# traffic_lights.net
KiCad netlist of a schematic drawn in EAGLE
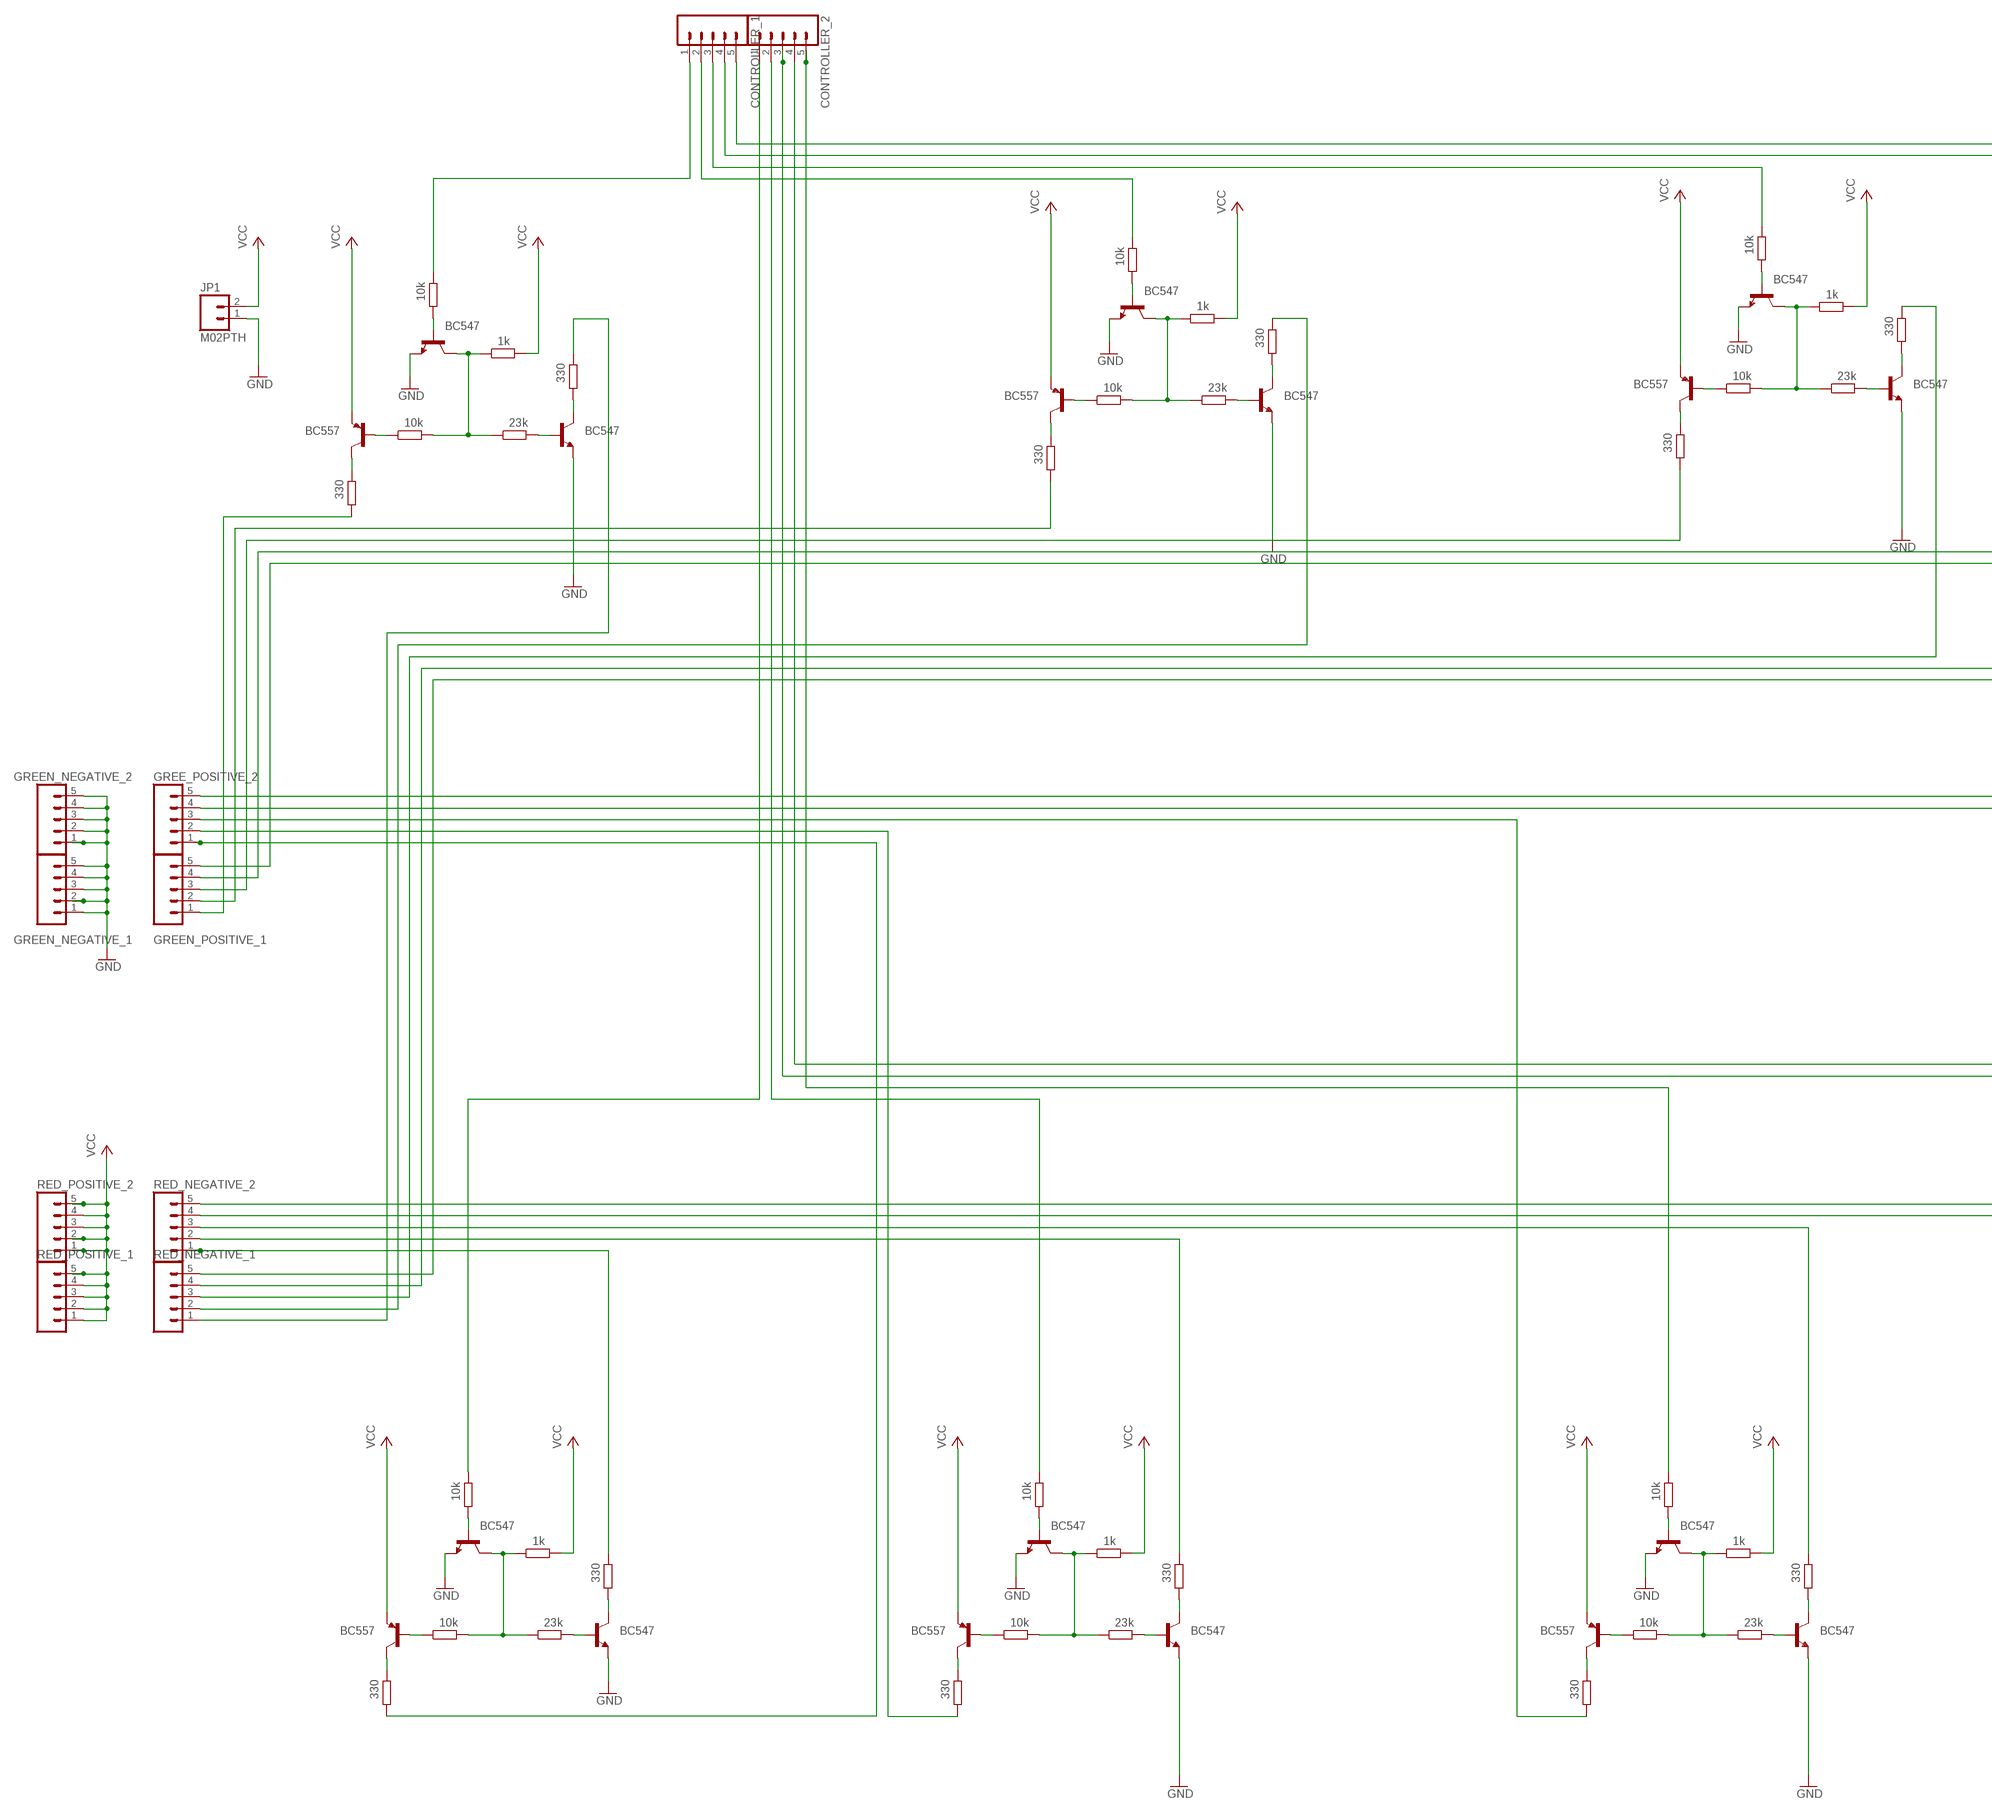
[diagram p0: schematic, sheet 1, part 1 of 2]
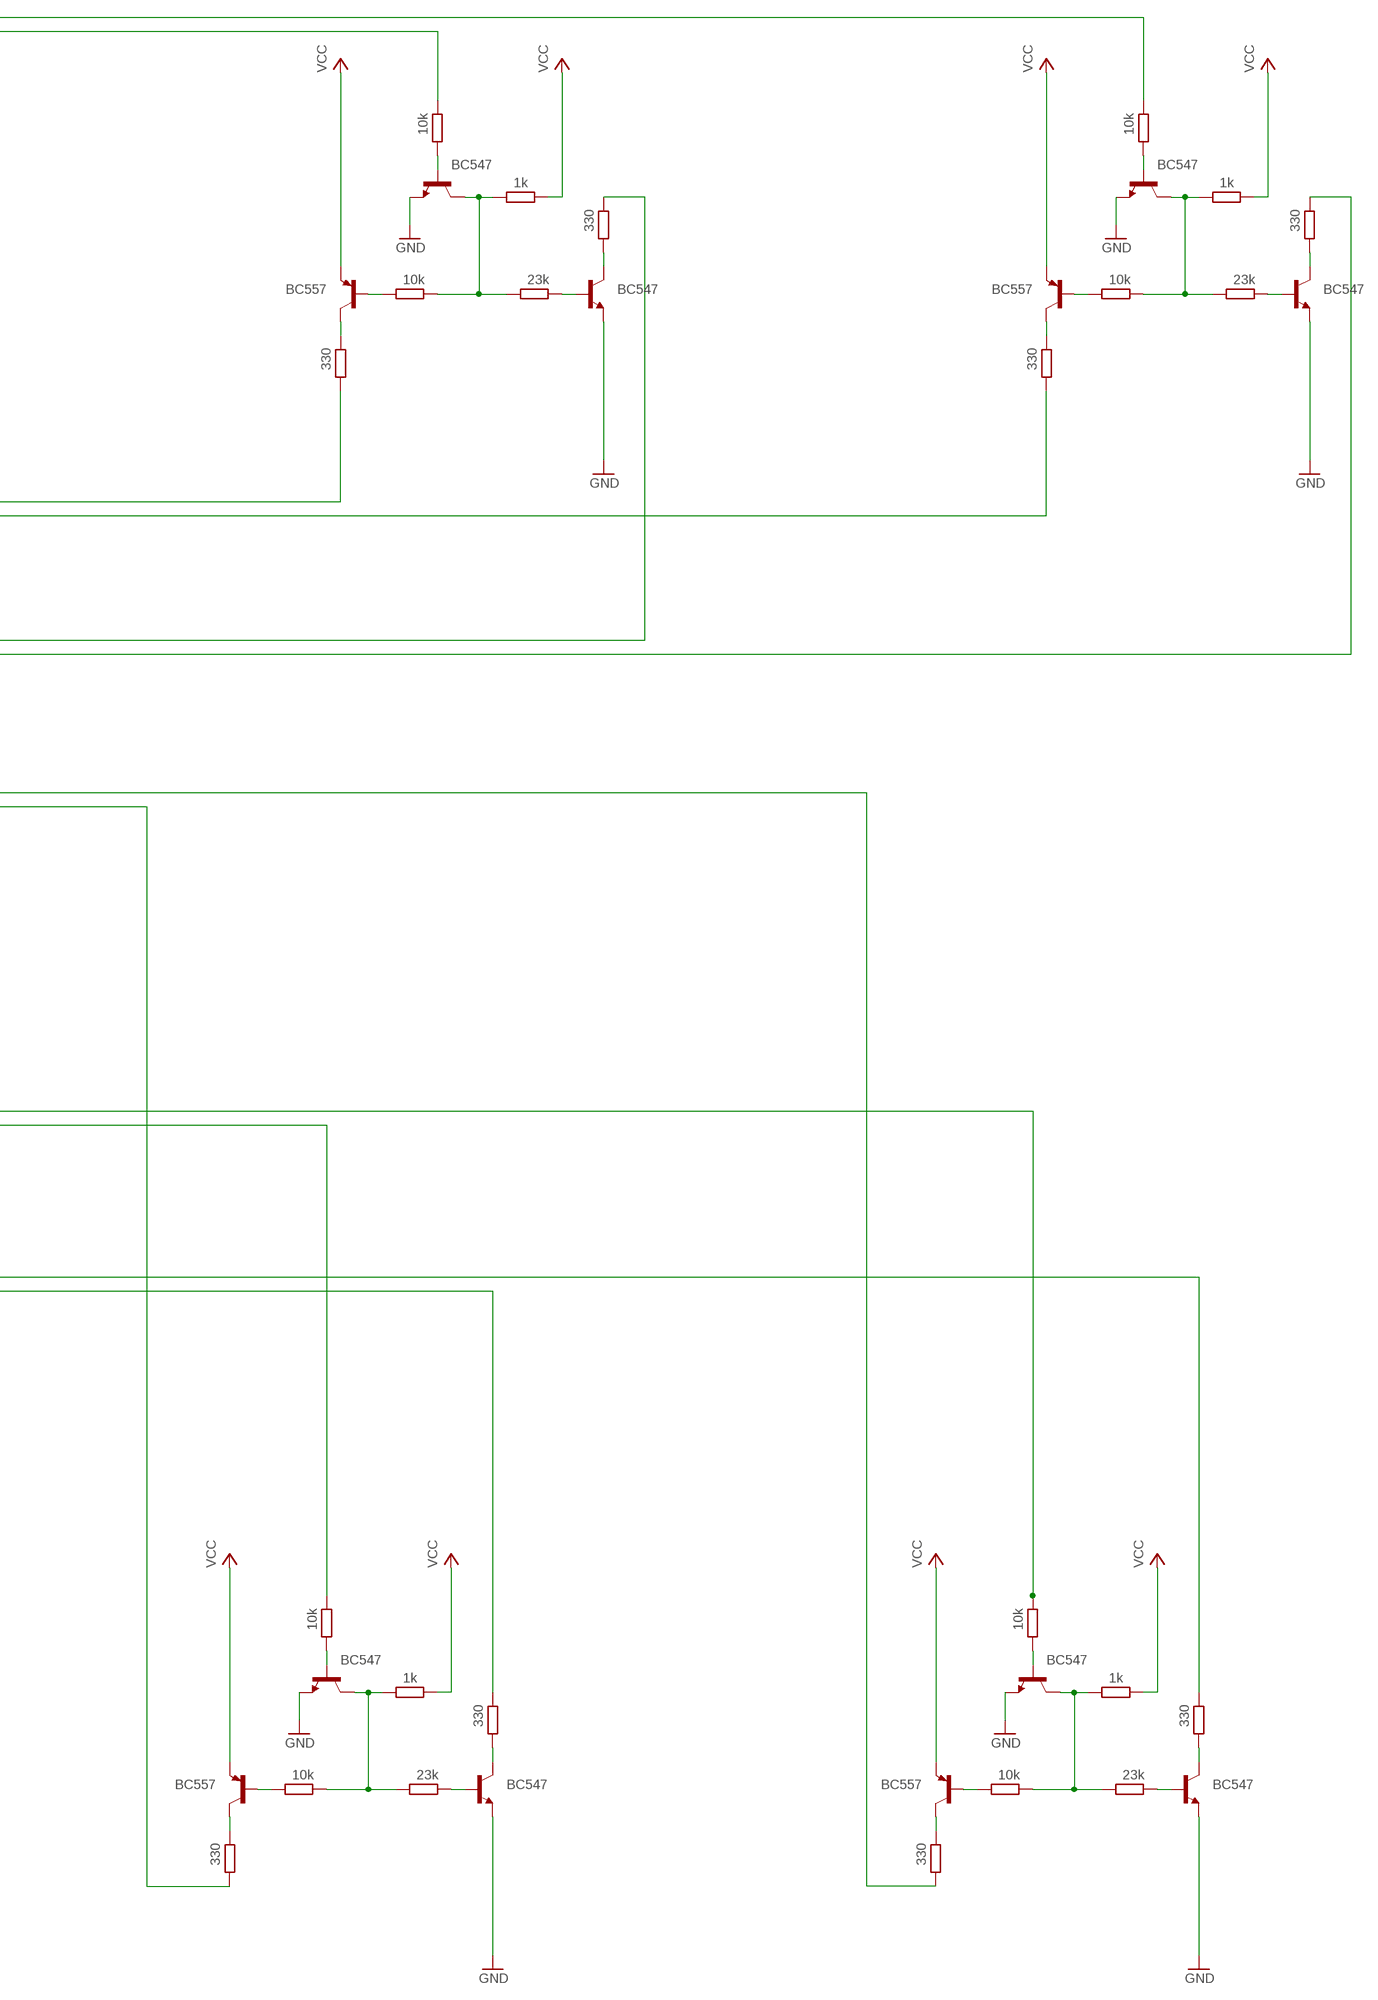
[diagram p1: schematic, sheet 1, part 2 of 2]

(export (version "E")
  (design (tool "Eeschema 10.0.6"))
  (components
    (comp (ref "CONTROLLER_1")
      (value "M05PTH")
      (footprint "eagle-import:1X05")
      (libsource (lib "eagle-import") (part "M05PTH"))
    )
    (comp (ref "CONTROLLER_2")
      (value "M05PTH")
      (footprint "eagle-import:1X05")
      (libsource (lib "eagle-import") (part "M05PTH"))
    )
    (comp (ref "GREEN_NEGATIVE_1")
      (value "M05PTH")
      (footprint "eagle-import:1X05")
      (libsource (lib "eagle-import") (part "M05PTH"))
    )
    (comp (ref "GREEN_NEGATIVE_2")
      (value "M05PTH")
      (footprint "eagle-import:1X05")
      (libsource (lib "eagle-import") (part "M05PTH"))
    )
    (comp (ref "GREEN_POSITIVE_1")
      (value "M05PTH")
      (footprint "eagle-import:1X05")
      (libsource (lib "eagle-import") (part "M05PTH"))
    )
    (comp (ref "GREE_POSITIVE_2")
      (value "M05PTH")
      (footprint "eagle-import:1X05")
      (libsource (lib "eagle-import") (part "M05PTH"))
    )
    (comp (ref "JP1")
      (value "M02PTH")
      (footprint "eagle-import:1X02")
      (libsource (lib "eagle-import") (part "M02PTH"))
    )
    (comp (ref "RC1")
      (value "10k")
      (footprint "eagle-import:0207_10")
      (libsource (lib "eagle-import") (part "R-EU_0207/10"))
    )
    (comp (ref "RC2")
      (value "1k")
      (footprint "eagle-import:0207_10")
      (libsource (lib "eagle-import") (part "R-EU_0207/10"))
    )
    (comp (ref "RC3")
      (value "23k")
      (footprint "eagle-import:0207_10")
      (libsource (lib "eagle-import") (part "R-EU_0207/10"))
    )
    (comp (ref "RC4")
      (value "10k")
      (footprint "eagle-import:0207_10")
      (libsource (lib "eagle-import") (part "R-EU_0207/10"))
    )
    (comp (ref "RC5")
      (value "330")
      (footprint "eagle-import:0207_10")
      (libsource (lib "eagle-import") (part "R-EU_0207/10"))
    )
    (comp (ref "RC6")
      (value "330")
      (footprint "eagle-import:0207_10")
      (libsource (lib "eagle-import") (part "R-EU_0207/10"))
    )
    (comp (ref "RC21")
      (value "10k")
      (footprint "eagle-import:0207_10")
      (libsource (lib "eagle-import") (part "R-EU_0207/10"))
    )
    (comp (ref "RC22")
      (value "1k")
      (footprint "eagle-import:0207_10")
      (libsource (lib "eagle-import") (part "R-EU_0207/10"))
    )
    (comp (ref "RC23")
      (value "23k")
      (footprint "eagle-import:0207_10")
      (libsource (lib "eagle-import") (part "R-EU_0207/10"))
    )
    (comp (ref "RC24")
      (value "10k")
      (footprint "eagle-import:0207_10")
      (libsource (lib "eagle-import") (part "R-EU_0207/10"))
    )
    (comp (ref "RC25")
      (value "330")
      (footprint "eagle-import:0207_10")
      (libsource (lib "eagle-import") (part "R-EU_0207/10"))
    )
    (comp (ref "RC26")
      (value "330")
      (footprint "eagle-import:0207_10")
      (libsource (lib "eagle-import") (part "R-EU_0207/10"))
    )
    (comp (ref "RC31")
      (value "10k")
      (footprint "eagle-import:0207_10")
      (libsource (lib "eagle-import") (part "R-EU_0207/10"))
    )
    (comp (ref "RC32")
      (value "1k")
      (footprint "eagle-import:0207_10")
      (libsource (lib "eagle-import") (part "R-EU_0207/10"))
    )
    (comp (ref "RC33")
      (value "23k")
      (footprint "eagle-import:0207_10")
      (libsource (lib "eagle-import") (part "R-EU_0207/10"))
    )
    (comp (ref "RC34")
      (value "10k")
      (footprint "eagle-import:0207_10")
      (libsource (lib "eagle-import") (part "R-EU_0207/10"))
    )
    (comp (ref "RC35")
      (value "330")
      (footprint "eagle-import:0207_10")
      (libsource (lib "eagle-import") (part "R-EU_0207/10"))
    )
    (comp (ref "RC36")
      (value "330")
      (footprint "eagle-import:0207_10")
      (libsource (lib "eagle-import") (part "R-EU_0207/10"))
    )
    (comp (ref "RC41")
      (value "10k")
      (footprint "eagle-import:0207_10")
      (libsource (lib "eagle-import") (part "R-EU_0207/10"))
    )
    (comp (ref "RC42")
      (value "1k")
      (footprint "eagle-import:0207_10")
      (libsource (lib "eagle-import") (part "R-EU_0207/10"))
    )
    (comp (ref "RC43")
      (value "23k")
      (footprint "eagle-import:0207_10")
      (libsource (lib "eagle-import") (part "R-EU_0207/10"))
    )
    (comp (ref "RC44")
      (value "10k")
      (footprint "eagle-import:0207_10")
      (libsource (lib "eagle-import") (part "R-EU_0207/10"))
    )
    (comp (ref "RC45")
      (value "330")
      (footprint "eagle-import:0207_10")
      (libsource (lib "eagle-import") (part "R-EU_0207/10"))
    )
    (comp (ref "RC46")
      (value "330")
      (footprint "eagle-import:0207_10")
      (libsource (lib "eagle-import") (part "R-EU_0207/10"))
    )
    (comp (ref "RC51")
      (value "10k")
      (footprint "eagle-import:0207_10")
      (libsource (lib "eagle-import") (part "R-EU_0207/10"))
    )
    (comp (ref "RC52")
      (value "1k")
      (footprint "eagle-import:0207_10")
      (libsource (lib "eagle-import") (part "R-EU_0207/10"))
    )
    (comp (ref "RC53")
      (value "23k")
      (footprint "eagle-import:0207_10")
      (libsource (lib "eagle-import") (part "R-EU_0207/10"))
    )
    (comp (ref "RC54")
      (value "10k")
      (footprint "eagle-import:0207_10")
      (libsource (lib "eagle-import") (part "R-EU_0207/10"))
    )
    (comp (ref "RC55")
      (value "330")
      (footprint "eagle-import:0207_10")
      (libsource (lib "eagle-import") (part "R-EU_0207/10"))
    )
    (comp (ref "RC56")
      (value "330")
      (footprint "eagle-import:0207_10")
      (libsource (lib "eagle-import") (part "R-EU_0207/10"))
    )
    (comp (ref "RC61")
      (value "10k")
      (footprint "eagle-import:0207_10")
      (libsource (lib "eagle-import") (part "R-EU_0207/10"))
    )
    (comp (ref "RC62")
      (value "1k")
      (footprint "eagle-import:0207_10")
      (libsource (lib "eagle-import") (part "R-EU_0207/10"))
    )
    (comp (ref "RC63")
      (value "23k")
      (footprint "eagle-import:0207_10")
      (libsource (lib "eagle-import") (part "R-EU_0207/10"))
    )
    (comp (ref "RC64")
      (value "10k")
      (footprint "eagle-import:0207_10")
      (libsource (lib "eagle-import") (part "R-EU_0207/10"))
    )
    (comp (ref "RC65")
      (value "330")
      (footprint "eagle-import:0207_10")
      (libsource (lib "eagle-import") (part "R-EU_0207/10"))
    )
    (comp (ref "RC66")
      (value "330")
      (footprint "eagle-import:0207_10")
      (libsource (lib "eagle-import") (part "R-EU_0207/10"))
    )
    (comp (ref "RC71")
      (value "10k")
      (footprint "eagle-import:0207_10")
      (libsource (lib "eagle-import") (part "R-EU_0207/10"))
    )
    (comp (ref "RC72")
      (value "1k")
      (footprint "eagle-import:0207_10")
      (libsource (lib "eagle-import") (part "R-EU_0207/10"))
    )
    (comp (ref "RC73")
      (value "23k")
      (footprint "eagle-import:0207_10")
      (libsource (lib "eagle-import") (part "R-EU_0207/10"))
    )
    (comp (ref "RC74")
      (value "10k")
      (footprint "eagle-import:0207_10")
      (libsource (lib "eagle-import") (part "R-EU_0207/10"))
    )
    (comp (ref "RC75")
      (value "330")
      (footprint "eagle-import:0207_10")
      (libsource (lib "eagle-import") (part "R-EU_0207/10"))
    )
    (comp (ref "RC76")
      (value "330")
      (footprint "eagle-import:0207_10")
      (libsource (lib "eagle-import") (part "R-EU_0207/10"))
    )
    (comp (ref "RC81")
      (value "10k")
      (footprint "eagle-import:0207_10")
      (libsource (lib "eagle-import") (part "R-EU_0207/10"))
    )
    (comp (ref "RC82")
      (value "1k")
      (footprint "eagle-import:0207_10")
      (libsource (lib "eagle-import") (part "R-EU_0207/10"))
    )
    (comp (ref "RC83")
      (value "23k")
      (footprint "eagle-import:0207_10")
      (libsource (lib "eagle-import") (part "R-EU_0207/10"))
    )
    (comp (ref "RC84")
      (value "10k")
      (footprint "eagle-import:0207_10")
      (libsource (lib "eagle-import") (part "R-EU_0207/10"))
    )
    (comp (ref "RC85")
      (value "330")
      (footprint "eagle-import:0207_10")
      (libsource (lib "eagle-import") (part "R-EU_0207/10"))
    )
    (comp (ref "RC86")
      (value "330")
      (footprint "eagle-import:0207_10")
      (libsource (lib "eagle-import") (part "R-EU_0207/10"))
    )
    (comp (ref "RC91")
      (value "10k")
      (footprint "eagle-import:0207_10")
      (libsource (lib "eagle-import") (part "R-EU_0207/10"))
    )
    (comp (ref "RC92")
      (value "1k")
      (footprint "eagle-import:0207_10")
      (libsource (lib "eagle-import") (part "R-EU_0207/10"))
    )
    (comp (ref "RC93")
      (value "23k")
      (footprint "eagle-import:0207_10")
      (libsource (lib "eagle-import") (part "R-EU_0207/10"))
    )
    (comp (ref "RC94")
      (value "10k")
      (footprint "eagle-import:0207_10")
      (libsource (lib "eagle-import") (part "R-EU_0207/10"))
    )
    (comp (ref "RC95")
      (value "330")
      (footprint "eagle-import:0207_10")
      (libsource (lib "eagle-import") (part "R-EU_0207/10"))
    )
    (comp (ref "RC96")
      (value "330")
      (footprint "eagle-import:0207_10")
      (libsource (lib "eagle-import") (part "R-EU_0207/10"))
    )
    (comp (ref "RC101")
      (value "10k")
      (footprint "eagle-import:0207_10")
      (libsource (lib "eagle-import") (part "R-EU_0207/10"))
    )
    (comp (ref "RC102")
      (value "1k")
      (footprint "eagle-import:0207_10")
      (libsource (lib "eagle-import") (part "R-EU_0207/10"))
    )
    (comp (ref "RC103")
      (value "23k")
      (footprint "eagle-import:0207_10")
      (libsource (lib "eagle-import") (part "R-EU_0207/10"))
    )
    (comp (ref "RC104")
      (value "10k")
      (footprint "eagle-import:0207_10")
      (libsource (lib "eagle-import") (part "R-EU_0207/10"))
    )
    (comp (ref "RC105")
      (value "330")
      (footprint "eagle-import:0207_10")
      (libsource (lib "eagle-import") (part "R-EU_0207/10"))
    )
    (comp (ref "RC106")
      (value "330")
      (footprint "eagle-import:0207_10")
      (libsource (lib "eagle-import") (part "R-EU_0207/10"))
    )
    (comp (ref "RED_NEGATIVE_1")
      (value "M05PTH")
      (footprint "eagle-import:1X05")
      (libsource (lib "eagle-import") (part "M05PTH"))
    )
    (comp (ref "RED_NEGATIVE_2")
      (value "M05PTH")
      (footprint "eagle-import:1X05")
      (libsource (lib "eagle-import") (part "M05PTH"))
    )
    (comp (ref "RED_POSITIVE_1")
      (value "M05PTH")
      (footprint "eagle-import:1X05")
      (libsource (lib "eagle-import") (part "M05PTH"))
    )
    (comp (ref "RED_POSITIVE_2")
      (value "M05PTH")
      (footprint "eagle-import:1X05")
      (libsource (lib "eagle-import") (part "M05PTH"))
    )
    (comp (ref "TCTRL1")
      (value "BC547")
      (footprint "eagle-import:TO92")
      (libsource (lib "eagle-import") (part "BC547"))
    )
    (comp (ref "TCTRL2")
      (value "BC547")
      (footprint "eagle-import:TO92")
      (libsource (lib "eagle-import") (part "BC547"))
    )
    (comp (ref "TCTRL3")
      (value "BC547")
      (footprint "eagle-import:TO92")
      (libsource (lib "eagle-import") (part "BC547"))
    )
    (comp (ref "TCTRL4")
      (value "BC547")
      (footprint "eagle-import:TO92")
      (libsource (lib "eagle-import") (part "BC547"))
    )
    (comp (ref "TCTRL5")
      (value "BC547")
      (footprint "eagle-import:TO92")
      (libsource (lib "eagle-import") (part "BC547"))
    )
    (comp (ref "TCTRL6")
      (value "BC547")
      (footprint "eagle-import:TO92")
      (libsource (lib "eagle-import") (part "BC547"))
    )
    (comp (ref "TCTRL7")
      (value "BC547")
      (footprint "eagle-import:TO92")
      (libsource (lib "eagle-import") (part "BC547"))
    )
    (comp (ref "TCTRL8")
      (value "BC547")
      (footprint "eagle-import:TO92")
      (libsource (lib "eagle-import") (part "BC547"))
    )
    (comp (ref "TCTRL9")
      (value "BC547")
      (footprint "eagle-import:TO92")
      (libsource (lib "eagle-import") (part "BC547"))
    )
    (comp (ref "TCTRL10")
      (value "BC547")
      (footprint "eagle-import:TO92")
      (libsource (lib "eagle-import") (part "BC547"))
    )
    (comp (ref "TGR1")
      (value "BC547")
      (footprint "eagle-import:TO92")
      (libsource (lib "eagle-import") (part "BC547"))
    )
    (comp (ref "TGR2")
      (value "BC547")
      (footprint "eagle-import:TO92")
      (libsource (lib "eagle-import") (part "BC547"))
    )
    (comp (ref "TGR3")
      (value "BC547")
      (footprint "eagle-import:TO92")
      (libsource (lib "eagle-import") (part "BC547"))
    )
    (comp (ref "TGR4")
      (value "BC547")
      (footprint "eagle-import:TO92")
      (libsource (lib "eagle-import") (part "BC547"))
    )
    (comp (ref "TGR5")
      (value "BC547")
      (footprint "eagle-import:TO92")
      (libsource (lib "eagle-import") (part "BC547"))
    )
    (comp (ref "TGR6")
      (value "BC547")
      (footprint "eagle-import:TO92")
      (libsource (lib "eagle-import") (part "BC547"))
    )
    (comp (ref "TGR7")
      (value "BC547")
      (footprint "eagle-import:TO92")
      (libsource (lib "eagle-import") (part "BC547"))
    )
    (comp (ref "TGR8")
      (value "BC547")
      (footprint "eagle-import:TO92")
      (libsource (lib "eagle-import") (part "BC547"))
    )
    (comp (ref "TGR9")
      (value "BC547")
      (footprint "eagle-import:TO92")
      (libsource (lib "eagle-import") (part "BC547"))
    )
    (comp (ref "TGR10")
      (value "BC547")
      (footprint "eagle-import:TO92")
      (libsource (lib "eagle-import") (part "BC547"))
    )
    (comp (ref "TR1")
      (value "BC557")
      (footprint "eagle-import:TO92")
      (libsource (lib "eagle-import") (part "BC557"))
    )
    (comp (ref "TR2")
      (value "BC557")
      (footprint "eagle-import:TO92")
      (libsource (lib "eagle-import") (part "BC557"))
    )
    (comp (ref "TR3")
      (value "BC557")
      (footprint "eagle-import:TO92")
      (libsource (lib "eagle-import") (part "BC557"))
    )
    (comp (ref "TR4")
      (value "BC557")
      (footprint "eagle-import:TO92")
      (libsource (lib "eagle-import") (part "BC557"))
    )
    (comp (ref "TR5")
      (value "BC557")
      (footprint "eagle-import:TO92")
      (libsource (lib "eagle-import") (part "BC557"))
    )
    (comp (ref "TR6")
      (value "BC557")
      (footprint "eagle-import:TO92")
      (libsource (lib "eagle-import") (part "BC557"))
    )
    (comp (ref "TR7")
      (value "BC557")
      (footprint "eagle-import:TO92")
      (libsource (lib "eagle-import") (part "BC557"))
    )
    (comp (ref "TR8")
      (value "BC557")
      (footprint "eagle-import:TO92")
      (libsource (lib "eagle-import") (part "BC557"))
    )
    (comp (ref "TR9")
      (value "BC557")
      (footprint "eagle-import:TO92")
      (libsource (lib "eagle-import") (part "BC557"))
    )
    (comp (ref "TR10")
      (value "BC557")
      (footprint "eagle-import:TO92")
      (libsource (lib "eagle-import") (part "BC557"))
    )
  )
  (nets
    (net (code "1") (name "GND") (class "Default")
      (node (ref "GREEN_NEGATIVE_1") (pin "1") (pinfunction "1_1") (pintype "passive"))
      (node (ref "GREEN_NEGATIVE_1") (pin "2") (pinfunction "2_2") (pintype "passive"))
      (node (ref "GREEN_NEGATIVE_1") (pin "3") (pinfunction "3_3") (pintype "passive"))
      (node (ref "GREEN_NEGATIVE_1") (pin "4") (pinfunction "4_4") (pintype "passive"))
      (node (ref "GREEN_NEGATIVE_1") (pin "5") (pinfunction "5_5") (pintype "passive"))
      (node (ref "GREEN_NEGATIVE_2") (pin "1") (pinfunction "1_1") (pintype "passive"))
      (node (ref "GREEN_NEGATIVE_2") (pin "2") (pinfunction "2_2") (pintype "passive"))
      (node (ref "GREEN_NEGATIVE_2") (pin "3") (pinfunction "3_3") (pintype "passive"))
      (node (ref "GREEN_NEGATIVE_2") (pin "4") (pinfunction "4_4") (pintype "passive"))
      (node (ref "GREEN_NEGATIVE_2") (pin "5") (pinfunction "5_5") (pintype "passive"))
      (node (ref "JP1") (pin "1") (pinfunction "1_1") (pintype "passive"))
      (node (ref "TCTRL1") (pin "1") (pinfunction "E_1") (pintype "passive"))
      (node (ref "TCTRL10") (pin "1") (pinfunction "E_1") (pintype "passive"))
      (node (ref "TCTRL2") (pin "1") (pinfunction "E_1") (pintype "passive"))
      (node (ref "TCTRL3") (pin "1") (pinfunction "E_1") (pintype "passive"))
      (node (ref "TCTRL4") (pin "1") (pinfunction "E_1") (pintype "passive"))
      (node (ref "TCTRL5") (pin "1") (pinfunction "E_1") (pintype "passive"))
      (node (ref "TCTRL6") (pin "1") (pinfunction "E_1") (pintype "passive"))
      (node (ref "TCTRL7") (pin "1") (pinfunction "E_1") (pintype "passive"))
      (node (ref "TCTRL8") (pin "1") (pinfunction "E_1") (pintype "passive"))
      (node (ref "TCTRL9") (pin "1") (pinfunction "E_1") (pintype "passive"))
      (node (ref "TGR1") (pin "1") (pinfunction "E_1") (pintype "passive"))
      (node (ref "TGR10") (pin "1") (pinfunction "E_1") (pintype "passive"))
      (node (ref "TGR2") (pin "1") (pinfunction "E_1") (pintype "passive"))
      (node (ref "TGR3") (pin "1") (pinfunction "E_1") (pintype "passive"))
      (node (ref "TGR4") (pin "1") (pinfunction "E_1") (pintype "passive"))
      (node (ref "TGR5") (pin "1") (pinfunction "E_1") (pintype "passive"))
      (node (ref "TGR6") (pin "1") (pinfunction "E_1") (pintype "passive"))
      (node (ref "TGR7") (pin "1") (pinfunction "E_1") (pintype "passive"))
      (node (ref "TGR8") (pin "1") (pinfunction "E_1") (pintype "passive"))
      (node (ref "TGR9") (pin "1") (pinfunction "E_1") (pintype "passive"))
    )
    (net (code "2") (name "Net-(CONTROLLER_1-Pad1)") (class "Default")
      (node (ref "CONTROLLER_1") (pin "1") (pinfunction "1_1") (pintype "passive"))
      (node (ref "RC1") (pin "2") (pinfunction "2_2") (pintype "passive"))
    )
    (net (code "3") (name "Net-(CONTROLLER_1-Pad2)") (class "Default")
      (node (ref "CONTROLLER_1") (pin "2") (pinfunction "2_2") (pintype "passive"))
      (node (ref "RC21") (pin "2") (pinfunction "2_2") (pintype "passive"))
    )
    (net (code "4") (name "Net-(CONTROLLER_1-Pad3)") (class "Default")
      (node (ref "CONTROLLER_1") (pin "3") (pinfunction "3_3") (pintype "passive"))
      (node (ref "RC31") (pin "2") (pinfunction "2_2") (pintype "passive"))
    )
    (net (code "5") (name "Net-(CONTROLLER_1-Pad4)") (class "Default")
      (node (ref "CONTROLLER_1") (pin "4") (pinfunction "4_4") (pintype "passive"))
      (node (ref "RC41") (pin "2") (pinfunction "2_2") (pintype "passive"))
    )
    (net (code "6") (name "Net-(CONTROLLER_1-Pad5)") (class "Default")
      (node (ref "CONTROLLER_1") (pin "5") (pinfunction "5_5") (pintype "passive"))
      (node (ref "RC51") (pin "2") (pinfunction "2_2") (pintype "passive"))
    )
    (net (code "7") (name "Net-(CONTROLLER_2-Pad1)") (class "Default")
      (node (ref "CONTROLLER_2") (pin "1") (pinfunction "1_1") (pintype "passive"))
      (node (ref "RC61") (pin "2") (pinfunction "2_2") (pintype "passive"))
    )
    (net (code "8") (name "Net-(CONTROLLER_2-Pad2)") (class "Default")
      (node (ref "CONTROLLER_2") (pin "2") (pinfunction "2_2") (pintype "passive"))
      (node (ref "RC71") (pin "2") (pinfunction "2_2") (pintype "passive"))
    )
    (net (code "9") (name "Net-(CONTROLLER_2-Pad3)") (class "Default")
      (node (ref "CONTROLLER_2") (pin "3") (pinfunction "3_3") (pintype "passive"))
      (node (ref "RC91") (pin "2") (pinfunction "2_2") (pintype "passive"))
    )
    (net (code "10") (name "Net-(CONTROLLER_2-Pad4)") (class "Default")
      (node (ref "CONTROLLER_2") (pin "4") (pinfunction "4_4") (pintype "passive"))
      (node (ref "RC101") (pin "2") (pinfunction "2_2") (pintype "passive"))
    )
    (net (code "11") (name "Net-(CONTROLLER_2-Pad5)") (class "Default")
      (node (ref "CONTROLLER_2") (pin "5") (pinfunction "5_5") (pintype "passive"))
      (node (ref "RC81") (pin "2") (pinfunction "2_2") (pintype "passive"))
    )
    (net (code "12") (name "Net-(GREEN_POSITIVE_1-Pad1)") (class "Default")
      (node (ref "GREEN_POSITIVE_1") (pin "1") (pinfunction "1_1") (pintype "passive"))
      (node (ref "RC6") (pin "1") (pinfunction "1_1") (pintype "passive"))
    )
    (net (code "13") (name "Net-(GREEN_POSITIVE_1-Pad2)") (class "Default")
      (node (ref "GREEN_POSITIVE_1") (pin "2") (pinfunction "2_2") (pintype "passive"))
      (node (ref "RC26") (pin "1") (pinfunction "1_1") (pintype "passive"))
    )
    (net (code "14") (name "Net-(GREEN_POSITIVE_1-Pad3)") (class "Default")
      (node (ref "GREEN_POSITIVE_1") (pin "3") (pinfunction "3_3") (pintype "passive"))
      (node (ref "RC36") (pin "1") (pinfunction "1_1") (pintype "passive"))
    )
    (net (code "15") (name "Net-(GREEN_POSITIVE_1-Pad4)") (class "Default")
      (node (ref "GREEN_POSITIVE_1") (pin "4") (pinfunction "4_4") (pintype "passive"))
      (node (ref "RC46") (pin "1") (pinfunction "1_1") (pintype "passive"))
    )
    (net (code "16") (name "Net-(GREEN_POSITIVE_1-Pad5)") (class "Default")
      (node (ref "GREEN_POSITIVE_1") (pin "5") (pinfunction "5_5") (pintype "passive"))
      (node (ref "RC56") (pin "1") (pinfunction "1_1") (pintype "passive"))
    )
    (net (code "17") (name "Net-(GREE_POSITIVE_2-Pad1)") (class "Default")
      (node (ref "GREE_POSITIVE_2") (pin "1") (pinfunction "1_1") (pintype "passive"))
      (node (ref "RC66") (pin "1") (pinfunction "1_1") (pintype "passive"))
    )
    (net (code "18") (name "Net-(GREE_POSITIVE_2-Pad2)") (class "Default")
      (node (ref "GREE_POSITIVE_2") (pin "2") (pinfunction "2_2") (pintype "passive"))
      (node (ref "RC76") (pin "1") (pinfunction "1_1") (pintype "passive"))
    )
    (net (code "19") (name "Net-(GREE_POSITIVE_2-Pad3)") (class "Default")
      (node (ref "GREE_POSITIVE_2") (pin "3") (pinfunction "3_3") (pintype "passive"))
      (node (ref "RC86") (pin "1") (pinfunction "1_1") (pintype "passive"))
    )
    (net (code "20") (name "Net-(GREE_POSITIVE_2-Pad4)") (class "Default")
      (node (ref "GREE_POSITIVE_2") (pin "4") (pinfunction "4_4") (pintype "passive"))
      (node (ref "RC96") (pin "1") (pinfunction "1_1") (pintype "passive"))
    )
    (net (code "21") (name "Net-(GREE_POSITIVE_2-Pad5)") (class "Default")
      (node (ref "GREE_POSITIVE_2") (pin "5") (pinfunction "5_5") (pintype "passive"))
      (node (ref "RC106") (pin "1") (pinfunction "1_1") (pintype "passive"))
    )
    (net (code "22") (name "Net-(RC5-Pad2)") (class "Default")
      (node (ref "RC5") (pin "2") (pinfunction "2_2") (pintype "passive"))
      (node (ref "RED_NEGATIVE_1") (pin "1") (pinfunction "1_1") (pintype "passive"))
    )
    (net (code "23") (name "Net-(RC25-Pad2)") (class "Default")
      (node (ref "RC25") (pin "2") (pinfunction "2_2") (pintype "passive"))
      (node (ref "RED_NEGATIVE_1") (pin "2") (pinfunction "2_2") (pintype "passive"))
    )
    (net (code "24") (name "Net-(RC35-Pad2)") (class "Default")
      (node (ref "RC35") (pin "2") (pinfunction "2_2") (pintype "passive"))
      (node (ref "RED_NEGATIVE_1") (pin "3") (pinfunction "3_3") (pintype "passive"))
    )
    (net (code "25") (name "Net-(RC45-Pad2)") (class "Default")
      (node (ref "RC45") (pin "2") (pinfunction "2_2") (pintype "passive"))
      (node (ref "RED_NEGATIVE_1") (pin "4") (pinfunction "4_4") (pintype "passive"))
    )
    (net (code "26") (name "Net-(RC55-Pad2)") (class "Default")
      (node (ref "RC55") (pin "2") (pinfunction "2_2") (pintype "passive"))
      (node (ref "RED_NEGATIVE_1") (pin "5") (pinfunction "5_5") (pintype "passive"))
    )
    (net (code "27") (name "Net-(RC65-Pad2)") (class "Default")
      (node (ref "RC65") (pin "2") (pinfunction "2_2") (pintype "passive"))
      (node (ref "RED_NEGATIVE_2") (pin "1") (pinfunction "1_1") (pintype "passive"))
    )
    (net (code "28") (name "Net-(RC75-Pad2)") (class "Default")
      (node (ref "RC75") (pin "2") (pinfunction "2_2") (pintype "passive"))
      (node (ref "RED_NEGATIVE_2") (pin "2") (pinfunction "2_2") (pintype "passive"))
    )
    (net (code "29") (name "Net-(RC85-Pad2)") (class "Default")
      (node (ref "RC85") (pin "2") (pinfunction "2_2") (pintype "passive"))
      (node (ref "RED_NEGATIVE_2") (pin "3") (pinfunction "3_3") (pintype "passive"))
    )
    (net (code "30") (name "Net-(RC95-Pad2)") (class "Default")
      (node (ref "RC95") (pin "2") (pinfunction "2_2") (pintype "passive"))
      (node (ref "RED_NEGATIVE_2") (pin "4") (pinfunction "4_4") (pintype "passive"))
    )
    (net (code "31") (name "Net-(RC105-Pad2)") (class "Default")
      (node (ref "RC105") (pin "2") (pinfunction "2_2") (pintype "passive"))
      (node (ref "RED_NEGATIVE_2") (pin "5") (pinfunction "5_5") (pintype "passive"))
    )
    (net (code "32") (name "Net-(TCTRL1-B)") (class "Default")
      (node (ref "RC1") (pin "1") (pinfunction "1_1") (pintype "passive"))
      (node (ref "TCTRL1") (pin "2") (pinfunction "B_2") (pintype "passive"))
    )
    (net (code "33") (name "Net-(TCTRL1-C)") (class "Default")
      (node (ref "RC2") (pin "1") (pinfunction "1_1") (pintype "passive"))
      (node (ref "RC3") (pin "1") (pinfunction "1_1") (pintype "passive"))
      (node (ref "RC4") (pin "2") (pinfunction "2_2") (pintype "passive"))
      (node (ref "TCTRL1") (pin "3") (pinfunction "C_3") (pintype "passive"))
    )
    (net (code "34") (name "Net-(TCTRL2-B)") (class "Default")
      (node (ref "RC21") (pin "1") (pinfunction "1_1") (pintype "passive"))
      (node (ref "TCTRL2") (pin "2") (pinfunction "B_2") (pintype "passive"))
    )
    (net (code "35") (name "Net-(TCTRL2-C)") (class "Default")
      (node (ref "RC22") (pin "1") (pinfunction "1_1") (pintype "passive"))
      (node (ref "RC23") (pin "1") (pinfunction "1_1") (pintype "passive"))
      (node (ref "RC24") (pin "2") (pinfunction "2_2") (pintype "passive"))
      (node (ref "TCTRL2") (pin "3") (pinfunction "C_3") (pintype "passive"))
    )
    (net (code "36") (name "Net-(TCTRL3-B)") (class "Default")
      (node (ref "RC31") (pin "1") (pinfunction "1_1") (pintype "passive"))
      (node (ref "TCTRL3") (pin "2") (pinfunction "B_2") (pintype "passive"))
    )
    (net (code "37") (name "Net-(TCTRL3-C)") (class "Default")
      (node (ref "RC32") (pin "1") (pinfunction "1_1") (pintype "passive"))
      (node (ref "RC33") (pin "1") (pinfunction "1_1") (pintype "passive"))
      (node (ref "RC34") (pin "2") (pinfunction "2_2") (pintype "passive"))
      (node (ref "TCTRL3") (pin "3") (pinfunction "C_3") (pintype "passive"))
    )
    (net (code "38") (name "Net-(TCTRL4-B)") (class "Default")
      (node (ref "RC41") (pin "1") (pinfunction "1_1") (pintype "passive"))
      (node (ref "TCTRL4") (pin "2") (pinfunction "B_2") (pintype "passive"))
    )
    (net (code "39") (name "Net-(TCTRL4-C)") (class "Default")
      (node (ref "RC42") (pin "1") (pinfunction "1_1") (pintype "passive"))
      (node (ref "RC43") (pin "1") (pinfunction "1_1") (pintype "passive"))
      (node (ref "RC44") (pin "2") (pinfunction "2_2") (pintype "passive"))
      (node (ref "TCTRL4") (pin "3") (pinfunction "C_3") (pintype "passive"))
    )
    (net (code "40") (name "Net-(TCTRL5-B)") (class "Default")
      (node (ref "RC51") (pin "1") (pinfunction "1_1") (pintype "passive"))
      (node (ref "TCTRL5") (pin "2") (pinfunction "B_2") (pintype "passive"))
    )
    (net (code "41") (name "Net-(TCTRL5-C)") (class "Default")
      (node (ref "RC52") (pin "1") (pinfunction "1_1") (pintype "passive"))
      (node (ref "RC53") (pin "1") (pinfunction "1_1") (pintype "passive"))
      (node (ref "RC54") (pin "2") (pinfunction "2_2") (pintype "passive"))
      (node (ref "TCTRL5") (pin "3") (pinfunction "C_3") (pintype "passive"))
    )
    (net (code "42") (name "Net-(TCTRL6-B)") (class "Default")
      (node (ref "RC61") (pin "1") (pinfunction "1_1") (pintype "passive"))
      (node (ref "TCTRL6") (pin "2") (pinfunction "B_2") (pintype "passive"))
    )
    (net (code "43") (name "Net-(TCTRL6-C)") (class "Default")
      (node (ref "RC62") (pin "1") (pinfunction "1_1") (pintype "passive"))
      (node (ref "RC63") (pin "1") (pinfunction "1_1") (pintype "passive"))
      (node (ref "RC64") (pin "2") (pinfunction "2_2") (pintype "passive"))
      (node (ref "TCTRL6") (pin "3") (pinfunction "C_3") (pintype "passive"))
    )
    (net (code "44") (name "Net-(TCTRL7-B)") (class "Default")
      (node (ref "RC71") (pin "1") (pinfunction "1_1") (pintype "passive"))
      (node (ref "TCTRL7") (pin "2") (pinfunction "B_2") (pintype "passive"))
    )
    (net (code "45") (name "Net-(TCTRL7-C)") (class "Default")
      (node (ref "RC72") (pin "1") (pinfunction "1_1") (pintype "passive"))
      (node (ref "RC73") (pin "1") (pinfunction "1_1") (pintype "passive"))
      (node (ref "RC74") (pin "2") (pinfunction "2_2") (pintype "passive"))
      (node (ref "TCTRL7") (pin "3") (pinfunction "C_3") (pintype "passive"))
    )
    (net (code "46") (name "Net-(TCTRL8-B)") (class "Default")
      (node (ref "RC81") (pin "1") (pinfunction "1_1") (pintype "passive"))
      (node (ref "TCTRL8") (pin "2") (pinfunction "B_2") (pintype "passive"))
    )
    (net (code "47") (name "Net-(TCTRL8-C)") (class "Default")
      (node (ref "RC82") (pin "1") (pinfunction "1_1") (pintype "passive"))
      (node (ref "RC83") (pin "1") (pinfunction "1_1") (pintype "passive"))
      (node (ref "RC84") (pin "2") (pinfunction "2_2") (pintype "passive"))
      (node (ref "TCTRL8") (pin "3") (pinfunction "C_3") (pintype "passive"))
    )
    (net (code "48") (name "Net-(TCTRL9-B)") (class "Default")
      (node (ref "RC91") (pin "1") (pinfunction "1_1") (pintype "passive"))
      (node (ref "TCTRL9") (pin "2") (pinfunction "B_2") (pintype "passive"))
    )
    (net (code "49") (name "Net-(TCTRL9-C)") (class "Default")
      (node (ref "RC92") (pin "1") (pinfunction "1_1") (pintype "passive"))
      (node (ref "RC93") (pin "1") (pinfunction "1_1") (pintype "passive"))
      (node (ref "RC94") (pin "2") (pinfunction "2_2") (pintype "passive"))
      (node (ref "TCTRL9") (pin "3") (pinfunction "C_3") (pintype "passive"))
    )
    (net (code "50") (name "Net-(TCTRL10-B)") (class "Default")
      (node (ref "RC101") (pin "1") (pinfunction "1_1") (pintype "passive"))
      (node (ref "TCTRL10") (pin "2") (pinfunction "B_2") (pintype "passive"))
    )
    (net (code "51") (name "Net-(TCTRL10-C)") (class "Default")
      (node (ref "RC102") (pin "1") (pinfunction "1_1") (pintype "passive"))
      (node (ref "RC103") (pin "1") (pinfunction "1_1") (pintype "passive"))
      (node (ref "RC104") (pin "2") (pinfunction "2_2") (pintype "passive"))
      (node (ref "TCTRL10") (pin "3") (pinfunction "C_3") (pintype "passive"))
    )
    (net (code "52") (name "Net-(TGR1-B)") (class "Default")
      (node (ref "RC3") (pin "2") (pinfunction "2_2") (pintype "passive"))
      (node (ref "TGR1") (pin "2") (pinfunction "B_2") (pintype "passive"))
    )
    (net (code "53") (name "Net-(TGR1-C)") (class "Default")
      (node (ref "RC5") (pin "1") (pinfunction "1_1") (pintype "passive"))
      (node (ref "TGR1") (pin "3") (pinfunction "C_3") (pintype "passive"))
    )
    (net (code "54") (name "Net-(TGR2-B)") (class "Default")
      (node (ref "RC23") (pin "2") (pinfunction "2_2") (pintype "passive"))
      (node (ref "TGR2") (pin "2") (pinfunction "B_2") (pintype "passive"))
    )
    (net (code "55") (name "Net-(TGR2-C)") (class "Default")
      (node (ref "RC25") (pin "1") (pinfunction "1_1") (pintype "passive"))
      (node (ref "TGR2") (pin "3") (pinfunction "C_3") (pintype "passive"))
    )
    (net (code "56") (name "Net-(TGR3-B)") (class "Default")
      (node (ref "RC33") (pin "2") (pinfunction "2_2") (pintype "passive"))
      (node (ref "TGR3") (pin "2") (pinfunction "B_2") (pintype "passive"))
    )
    (net (code "57") (name "Net-(TGR3-C)") (class "Default")
      (node (ref "RC35") (pin "1") (pinfunction "1_1") (pintype "passive"))
      (node (ref "TGR3") (pin "3") (pinfunction "C_3") (pintype "passive"))
    )
    (net (code "58") (name "Net-(TGR4-B)") (class "Default")
      (node (ref "RC43") (pin "2") (pinfunction "2_2") (pintype "passive"))
      (node (ref "TGR4") (pin "2") (pinfunction "B_2") (pintype "passive"))
    )
    (net (code "59") (name "Net-(TGR4-C)") (class "Default")
      (node (ref "RC45") (pin "1") (pinfunction "1_1") (pintype "passive"))
      (node (ref "TGR4") (pin "3") (pinfunction "C_3") (pintype "passive"))
    )
    (net (code "60") (name "Net-(TGR5-B)") (class "Default")
      (node (ref "RC53") (pin "2") (pinfunction "2_2") (pintype "passive"))
      (node (ref "TGR5") (pin "2") (pinfunction "B_2") (pintype "passive"))
    )
    (net (code "61") (name "Net-(TGR5-C)") (class "Default")
      (node (ref "RC55") (pin "1") (pinfunction "1_1") (pintype "passive"))
      (node (ref "TGR5") (pin "3") (pinfunction "C_3") (pintype "passive"))
    )
    (net (code "62") (name "Net-(TGR6-B)") (class "Default")
      (node (ref "RC63") (pin "2") (pinfunction "2_2") (pintype "passive"))
      (node (ref "TGR6") (pin "2") (pinfunction "B_2") (pintype "passive"))
    )
    (net (code "63") (name "Net-(TGR6-C)") (class "Default")
      (node (ref "RC65") (pin "1") (pinfunction "1_1") (pintype "passive"))
      (node (ref "TGR6") (pin "3") (pinfunction "C_3") (pintype "passive"))
    )
    (net (code "64") (name "Net-(TGR7-B)") (class "Default")
      (node (ref "RC73") (pin "2") (pinfunction "2_2") (pintype "passive"))
      (node (ref "TGR7") (pin "2") (pinfunction "B_2") (pintype "passive"))
    )
    (net (code "65") (name "Net-(TGR7-C)") (class "Default")
      (node (ref "RC75") (pin "1") (pinfunction "1_1") (pintype "passive"))
      (node (ref "TGR7") (pin "3") (pinfunction "C_3") (pintype "passive"))
    )
    (net (code "66") (name "Net-(TGR8-B)") (class "Default")
      (node (ref "RC83") (pin "2") (pinfunction "2_2") (pintype "passive"))
      (node (ref "TGR8") (pin "2") (pinfunction "B_2") (pintype "passive"))
    )
    (net (code "67") (name "Net-(TGR8-C)") (class "Default")
      (node (ref "RC85") (pin "1") (pinfunction "1_1") (pintype "passive"))
      (node (ref "TGR8") (pin "3") (pinfunction "C_3") (pintype "passive"))
    )
    (net (code "68") (name "Net-(TGR9-B)") (class "Default")
      (node (ref "RC93") (pin "2") (pinfunction "2_2") (pintype "passive"))
      (node (ref "TGR9") (pin "2") (pinfunction "B_2") (pintype "passive"))
    )
    (net (code "69") (name "Net-(TGR9-C)") (class "Default")
      (node (ref "RC95") (pin "1") (pinfunction "1_1") (pintype "passive"))
      (node (ref "TGR9") (pin "3") (pinfunction "C_3") (pintype "passive"))
    )
    (net (code "70") (name "Net-(TGR10-B)") (class "Default")
      (node (ref "RC103") (pin "2") (pinfunction "2_2") (pintype "passive"))
      (node (ref "TGR10") (pin "2") (pinfunction "B_2") (pintype "passive"))
    )
    (net (code "71") (name "Net-(TGR10-C)") (class "Default")
      (node (ref "RC105") (pin "1") (pinfunction "1_1") (pintype "passive"))
      (node (ref "TGR10") (pin "3") (pinfunction "C_3") (pintype "passive"))
    )
    (net (code "72") (name "Net-(TR1-B)") (class "Default")
      (node (ref "RC4") (pin "1") (pinfunction "1_1") (pintype "passive"))
      (node (ref "TR1") (pin "2") (pinfunction "B_2") (pintype "passive"))
    )
    (net (code "73") (name "Net-(TR1-C)") (class "Default")
      (node (ref "RC6") (pin "2") (pinfunction "2_2") (pintype "passive"))
      (node (ref "TR1") (pin "3") (pinfunction "C_3") (pintype "passive"))
    )
    (net (code "74") (name "Net-(TR2-B)") (class "Default")
      (node (ref "RC24") (pin "1") (pinfunction "1_1") (pintype "passive"))
      (node (ref "TR2") (pin "2") (pinfunction "B_2") (pintype "passive"))
    )
    (net (code "75") (name "Net-(TR2-C)") (class "Default")
      (node (ref "RC26") (pin "2") (pinfunction "2_2") (pintype "passive"))
      (node (ref "TR2") (pin "3") (pinfunction "C_3") (pintype "passive"))
    )
    (net (code "76") (name "Net-(TR3-B)") (class "Default")
      (node (ref "RC34") (pin "1") (pinfunction "1_1") (pintype "passive"))
      (node (ref "TR3") (pin "2") (pinfunction "B_2") (pintype "passive"))
    )
    (net (code "77") (name "Net-(TR3-C)") (class "Default")
      (node (ref "RC36") (pin "2") (pinfunction "2_2") (pintype "passive"))
      (node (ref "TR3") (pin "3") (pinfunction "C_3") (pintype "passive"))
    )
    (net (code "78") (name "Net-(TR4-B)") (class "Default")
      (node (ref "RC44") (pin "1") (pinfunction "1_1") (pintype "passive"))
      (node (ref "TR4") (pin "2") (pinfunction "B_2") (pintype "passive"))
    )
    (net (code "79") (name "Net-(TR4-C)") (class "Default")
      (node (ref "RC46") (pin "2") (pinfunction "2_2") (pintype "passive"))
      (node (ref "TR4") (pin "3") (pinfunction "C_3") (pintype "passive"))
    )
    (net (code "80") (name "Net-(TR5-B)") (class "Default")
      (node (ref "RC54") (pin "1") (pinfunction "1_1") (pintype "passive"))
      (node (ref "TR5") (pin "2") (pinfunction "B_2") (pintype "passive"))
    )
    (net (code "81") (name "Net-(TR5-C)") (class "Default")
      (node (ref "RC56") (pin "2") (pinfunction "2_2") (pintype "passive"))
      (node (ref "TR5") (pin "3") (pinfunction "C_3") (pintype "passive"))
    )
    (net (code "82") (name "Net-(TR6-B)") (class "Default")
      (node (ref "RC64") (pin "1") (pinfunction "1_1") (pintype "passive"))
      (node (ref "TR6") (pin "2") (pinfunction "B_2") (pintype "passive"))
    )
    (net (code "83") (name "Net-(TR6-C)") (class "Default")
      (node (ref "RC66") (pin "2") (pinfunction "2_2") (pintype "passive"))
      (node (ref "TR6") (pin "3") (pinfunction "C_3") (pintype "passive"))
    )
    (net (code "84") (name "Net-(TR7-B)") (class "Default")
      (node (ref "RC74") (pin "1") (pinfunction "1_1") (pintype "passive"))
      (node (ref "TR7") (pin "2") (pinfunction "B_2") (pintype "passive"))
    )
    (net (code "85") (name "Net-(TR7-C)") (class "Default")
      (node (ref "RC76") (pin "2") (pinfunction "2_2") (pintype "passive"))
      (node (ref "TR7") (pin "3") (pinfunction "C_3") (pintype "passive"))
    )
    (net (code "86") (name "Net-(TR8-B)") (class "Default")
      (node (ref "RC84") (pin "1") (pinfunction "1_1") (pintype "passive"))
      (node (ref "TR8") (pin "2") (pinfunction "B_2") (pintype "passive"))
    )
    (net (code "87") (name "Net-(TR8-C)") (class "Default")
      (node (ref "RC86") (pin "2") (pinfunction "2_2") (pintype "passive"))
      (node (ref "TR8") (pin "3") (pinfunction "C_3") (pintype "passive"))
    )
    (net (code "88") (name "Net-(TR9-B)") (class "Default")
      (node (ref "RC94") (pin "1") (pinfunction "1_1") (pintype "passive"))
      (node (ref "TR9") (pin "2") (pinfunction "B_2") (pintype "passive"))
    )
    (net (code "89") (name "Net-(TR9-C)") (class "Default")
      (node (ref "RC96") (pin "2") (pinfunction "2_2") (pintype "passive"))
      (node (ref "TR9") (pin "3") (pinfunction "C_3") (pintype "passive"))
    )
    (net (code "90") (name "Net-(TR10-B)") (class "Default")
      (node (ref "RC104") (pin "1") (pinfunction "1_1") (pintype "passive"))
      (node (ref "TR10") (pin "2") (pinfunction "B_2") (pintype "passive"))
    )
    (net (code "91") (name "Net-(TR10-C)") (class "Default")
      (node (ref "RC106") (pin "2") (pinfunction "2_2") (pintype "passive"))
      (node (ref "TR10") (pin "3") (pinfunction "C_3") (pintype "passive"))
    )
    (net (code "92") (name "VCC") (class "Default")
      (node (ref "JP1") (pin "2") (pinfunction "2_2") (pintype "passive"))
      (node (ref "RC102") (pin "2") (pinfunction "2_2") (pintype "passive"))
      (node (ref "RC2") (pin "2") (pinfunction "2_2") (pintype "passive"))
      (node (ref "RC22") (pin "2") (pinfunction "2_2") (pintype "passive"))
      (node (ref "RC32") (pin "2") (pinfunction "2_2") (pintype "passive"))
      (node (ref "RC42") (pin "2") (pinfunction "2_2") (pintype "passive"))
      (node (ref "RC52") (pin "2") (pinfunction "2_2") (pintype "passive"))
      (node (ref "RC62") (pin "2") (pinfunction "2_2") (pintype "passive"))
      (node (ref "RC72") (pin "2") (pinfunction "2_2") (pintype "passive"))
      (node (ref "RC82") (pin "2") (pinfunction "2_2") (pintype "passive"))
      (node (ref "RC92") (pin "2") (pinfunction "2_2") (pintype "passive"))
      (node (ref "RED_POSITIVE_1") (pin "1") (pinfunction "1_1") (pintype "passive"))
      (node (ref "RED_POSITIVE_1") (pin "2") (pinfunction "2_2") (pintype "passive"))
      (node (ref "RED_POSITIVE_1") (pin "3") (pinfunction "3_3") (pintype "passive"))
      (node (ref "RED_POSITIVE_1") (pin "4") (pinfunction "4_4") (pintype "passive"))
      (node (ref "RED_POSITIVE_1") (pin "5") (pinfunction "5_5") (pintype "passive"))
      (node (ref "RED_POSITIVE_2") (pin "1") (pinfunction "1_1") (pintype "passive"))
      (node (ref "RED_POSITIVE_2") (pin "2") (pinfunction "2_2") (pintype "passive"))
      (node (ref "RED_POSITIVE_2") (pin "3") (pinfunction "3_3") (pintype "passive"))
      (node (ref "RED_POSITIVE_2") (pin "4") (pinfunction "4_4") (pintype "passive"))
      (node (ref "RED_POSITIVE_2") (pin "5") (pinfunction "5_5") (pintype "passive"))
      (node (ref "TR1") (pin "1") (pinfunction "E_1") (pintype "passive"))
      (node (ref "TR10") (pin "1") (pinfunction "E_1") (pintype "passive"))
      (node (ref "TR2") (pin "1") (pinfunction "E_1") (pintype "passive"))
      (node (ref "TR3") (pin "1") (pinfunction "E_1") (pintype "passive"))
      (node (ref "TR4") (pin "1") (pinfunction "E_1") (pintype "passive"))
      (node (ref "TR5") (pin "1") (pinfunction "E_1") (pintype "passive"))
      (node (ref "TR6") (pin "1") (pinfunction "E_1") (pintype "passive"))
      (node (ref "TR7") (pin "1") (pinfunction "E_1") (pintype "passive"))
      (node (ref "TR8") (pin "1") (pinfunction "E_1") (pintype "passive"))
      (node (ref "TR9") (pin "1") (pinfunction "E_1") (pintype "passive"))
    )
  )
)
